# control_board.net
KiCad netlist of a schematic drawn in EAGLE
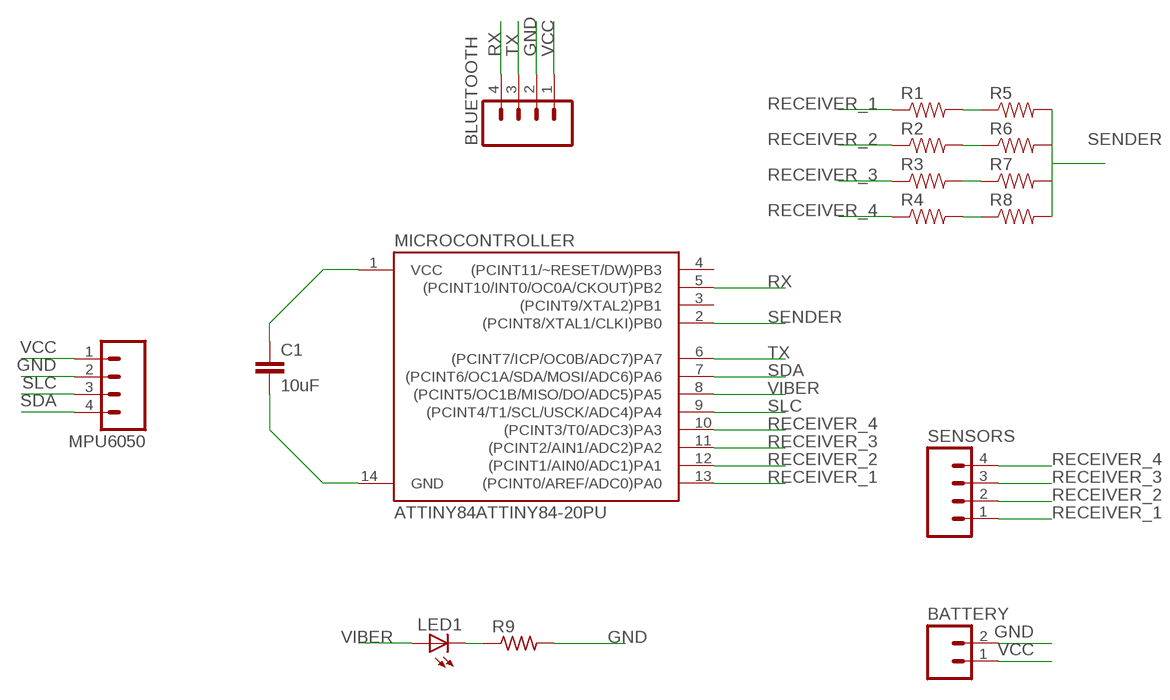
[diagram p0: schematic, sheet 1]

(export (version "E")
  (design (tool "Eeschema 10.0.6"))
  (components
    (comp (ref "BATTERY")
      (value "M02POLAR_LOCK")
      (footprint "eagle-import:MOLEX-1X2_LOCK")
      (libsource (lib "eagle-import") (part "M02POLAR_LOCK"))
    )
    (comp (ref "BLUETOOTH")
      (value "M04PTH")
      (footprint "eagle-import:1X04")
      (libsource (lib "eagle-import") (part "M04PTH"))
    )
    (comp (ref "C1")
      (value "10uF")
      (footprint "eagle-import:CAP-PTH-SMALL2")
      (libsource (lib "eagle-import") (part "CAPPTH2"))
    )
    (comp (ref "LED1")
      (value "LED5MM")
      (footprint "eagle-import:LED5MM")
      (libsource (lib "eagle-import") (part "LED5MM"))
    )
    (comp (ref "MICROCONTROLLER")
      (value "ATTINY84ATTINY84-20PU")
      (footprint "eagle-import:DIL14")
      (libsource (lib "eagle-import") (part "ATTINY84ATTINY84-20PU"))
    )
    (comp (ref "MPU6050")
      (value "M04PTH")
      (footprint "eagle-import:1X04")
      (libsource (lib "eagle-import") (part "M04PTH"))
    )
    (comp (ref "R1")
      (value "RESISTOREZ")
      (footprint "eagle-import:AXIAL-0.3EZ")
      (libsource (lib "eagle-import") (part "RESISTOREZ"))
    )
    (comp (ref "R2")
      (value "RESISTOREZ")
      (footprint "eagle-import:AXIAL-0.3EZ")
      (libsource (lib "eagle-import") (part "RESISTOREZ"))
    )
    (comp (ref "R3")
      (value "RESISTOREZ")
      (footprint "eagle-import:AXIAL-0.3EZ")
      (libsource (lib "eagle-import") (part "RESISTOREZ"))
    )
    (comp (ref "R4")
      (value "RESISTOREZ")
      (footprint "eagle-import:AXIAL-0.3EZ")
      (libsource (lib "eagle-import") (part "RESISTOREZ"))
    )
    (comp (ref "R5")
      (value "RESISTOREZ")
      (footprint "eagle-import:AXIAL-0.3EZ")
      (libsource (lib "eagle-import") (part "RESISTOREZ"))
    )
    (comp (ref "R6")
      (value "RESISTOREZ")
      (footprint "eagle-import:AXIAL-0.3EZ")
      (libsource (lib "eagle-import") (part "RESISTOREZ"))
    )
    (comp (ref "R7")
      (value "RESISTOREZ")
      (footprint "eagle-import:AXIAL-0.3EZ")
      (libsource (lib "eagle-import") (part "RESISTOREZ"))
    )
    (comp (ref "R8")
      (value "RESISTOREZ")
      (footprint "eagle-import:AXIAL-0.3EZ")
      (libsource (lib "eagle-import") (part "RESISTOREZ"))
    )
    (comp (ref "R9")
      (value "R-US_0207/10")
      (footprint "eagle-import:0207_10")
      (libsource (lib "eagle-import") (part "R-US_0207/10"))
    )
    (comp (ref "SENSORS")
      (value "M04PTH")
      (footprint "eagle-import:1X04")
      (libsource (lib "eagle-import") (part "M04PTH"))
    )
  )
  (nets
    (net (code "1") (name "/GND") (class "Default")
      (node (ref "BATTERY") (pin "2") (pinfunction "2_2") (pintype "passive"))
      (node (ref "BLUETOOTH") (pin "2") (pinfunction "2_2") (pintype "passive"))
      (node (ref "C1") (pin "2") (pinfunction "2_2") (pintype "passive"))
      (node (ref "MICROCONTROLLER") (pin "14") (pinfunction "GND_14") (pintype "bidirectional"))
      (node (ref "MPU6050") (pin "2") (pinfunction "2_2") (pintype "passive"))
      (node (ref "R9") (pin "2") (pinfunction "2_2") (pintype "passive"))
    )
    (net (code "2") (name "/RECEIVER_1") (class "Default")
      (node (ref "MICROCONTROLLER") (pin "13") (pinfunction "(PCINT0/AREF/ADC0)PA0_13") (pintype "bidirectional"))
      (node (ref "R1") (pin "P$1") (pinfunction "1_P$1") (pintype "passive"))
      (node (ref "SENSORS") (pin "1") (pinfunction "1_1") (pintype "passive"))
    )
    (net (code "3") (name "/RECEIVER_2") (class "Default")
      (node (ref "MICROCONTROLLER") (pin "12") (pinfunction "(PCINT1/AIN0/ADC1)PA1_12") (pintype "bidirectional"))
      (node (ref "R2") (pin "P$1") (pinfunction "1_P$1") (pintype "passive"))
      (node (ref "SENSORS") (pin "2") (pinfunction "2_2") (pintype "passive"))
    )
    (net (code "4") (name "/RECEIVER_3") (class "Default")
      (node (ref "MICROCONTROLLER") (pin "11") (pinfunction "(PCINT2/AIN1/ADC2)PA2_11") (pintype "bidirectional"))
      (node (ref "R3") (pin "P$1") (pinfunction "1_P$1") (pintype "passive"))
      (node (ref "SENSORS") (pin "3") (pinfunction "3_3") (pintype "passive"))
    )
    (net (code "5") (name "/RECEIVER_4") (class "Default")
      (node (ref "MICROCONTROLLER") (pin "10") (pinfunction "(PCINT3/T0/ADC3)PA3_10") (pintype "bidirectional"))
      (node (ref "R4") (pin "P$1") (pinfunction "1_P$1") (pintype "passive"))
      (node (ref "SENSORS") (pin "4") (pinfunction "4_4") (pintype "passive"))
    )
    (net (code "6") (name "/RX") (class "Default")
      (node (ref "BLUETOOTH") (pin "4") (pinfunction "4_4") (pintype "passive"))
      (node (ref "MICROCONTROLLER") (pin "5") (pinfunction "(PCINT10/INT0/OC0A/CKOUT)PB2_5") (pintype "bidirectional"))
    )
    (net (code "7") (name "/SDA") (class "Default")
      (node (ref "MICROCONTROLLER") (pin "7") (pinfunction "(PCINT6/OC1A/SDA/MOSI/ADC6)PA6_7") (pintype "bidirectional"))
      (node (ref "MPU6050") (pin "4") (pinfunction "4_4") (pintype "passive"))
    )
    (net (code "8") (name "/SENDER") (class "Default")
      (node (ref "MICROCONTROLLER") (pin "2") (pinfunction "(PCINT8/XTAL1/CLKI)PB0_2") (pintype "bidirectional"))
      (node (ref "R5") (pin "P$2") (pinfunction "2_P$2") (pintype "passive"))
      (node (ref "R6") (pin "P$2") (pinfunction "2_P$2") (pintype "passive"))
      (node (ref "R7") (pin "P$2") (pinfunction "2_P$2") (pintype "passive"))
      (node (ref "R8") (pin "P$2") (pinfunction "2_P$2") (pintype "passive"))
    )
    (net (code "9") (name "/SLC") (class "Default")
      (node (ref "MICROCONTROLLER") (pin "9") (pinfunction "(PCINT4/T1/SCL/USCK/ADC4)PA4_9") (pintype "bidirectional"))
      (node (ref "MPU6050") (pin "3") (pinfunction "3_3") (pintype "passive"))
    )
    (net (code "10") (name "/TX") (class "Default")
      (node (ref "BLUETOOTH") (pin "3") (pinfunction "3_3") (pintype "passive"))
      (node (ref "MICROCONTROLLER") (pin "6") (pinfunction "(PCINT7/ICP/OC0B/ADC7)PA7_6") (pintype "bidirectional"))
    )
    (net (code "11") (name "/VCC") (class "Default")
      (node (ref "BATTERY") (pin "1") (pinfunction "1_1") (pintype "passive"))
      (node (ref "BLUETOOTH") (pin "1") (pinfunction "1_1") (pintype "passive"))
      (node (ref "C1") (pin "1") (pinfunction "1_1") (pintype "passive"))
      (node (ref "MICROCONTROLLER") (pin "1") (pinfunction "VCC_1") (pintype "bidirectional"))
      (node (ref "MPU6050") (pin "1") (pinfunction "1_1") (pintype "passive"))
    )
    (net (code "12") (name "/VIBER") (class "Default")
      (node (ref "LED1") (pin "A") (pinfunction "A_A") (pintype "passive"))
      (node (ref "MICROCONTROLLER") (pin "8") (pinfunction "(PCINT5/OC1B/MISO/DO/ADC5)PA5_8") (pintype "bidirectional"))
    )
    (net (code "13") (name "Net-(LED1-C)") (class "Default")
      (node (ref "LED1") (pin "K") (pinfunction "C_K") (pintype "passive"))
      (node (ref "R9") (pin "1") (pinfunction "1_1") (pintype "passive"))
    )
    (net (code "14") (name "Net-(R1-2)") (class "Default")
      (node (ref "R1") (pin "P$2") (pinfunction "2_P$2") (pintype "passive"))
      (node (ref "R5") (pin "P$1") (pinfunction "1_P$1") (pintype "passive"))
    )
    (net (code "15") (name "Net-(R2-2)") (class "Default")
      (node (ref "R2") (pin "P$2") (pinfunction "2_P$2") (pintype "passive"))
      (node (ref "R6") (pin "P$1") (pinfunction "1_P$1") (pintype "passive"))
    )
    (net (code "16") (name "Net-(R3-2)") (class "Default")
      (node (ref "R3") (pin "P$2") (pinfunction "2_P$2") (pintype "passive"))
      (node (ref "R7") (pin "P$1") (pinfunction "1_P$1") (pintype "passive"))
    )
    (net (code "17") (name "Net-(R4-2)") (class "Default")
      (node (ref "R4") (pin "P$2") (pinfunction "2_P$2") (pintype "passive"))
      (node (ref "R8") (pin "P$1") (pinfunction "1_P$1") (pintype "passive"))
    )
    (net (code "18") (name "unconnected-(MICROCONTROLLER-(PCINT9{slash}XTAL2)PB1-Pad3)") (class "Default")
      (node (ref "MICROCONTROLLER") (pin "3") (pinfunction "(PCINT9/XTAL2)PB1_3") (pintype "bidirectional"))
    )
    (net (code "19") (name "unconnected-(MICROCONTROLLER-(PCINT11{slash}~{RESET{slash}DW})PB3-Pad4)") (class "Default")
      (node (ref "MICROCONTROLLER") (pin "4") (pinfunction "(PCINT11/~{RESET/DW})PB3_4") (pintype "bidirectional"))
    )
  )
)
